# lps22df.net
KiCad netlist of a schematic drawn in Altium Designer
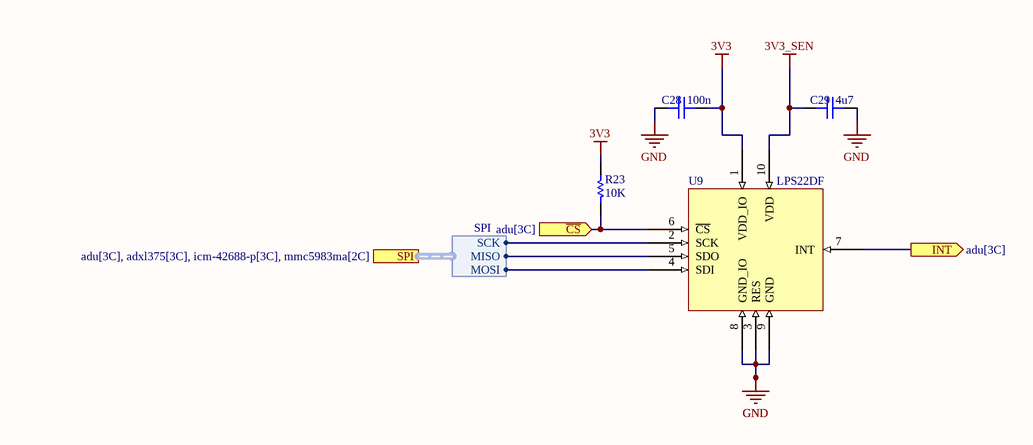
[diagram p0: lps22df.SchDoc]

(export (version "E")
  (design (tool "Eeschema 10.0.6"))
  (components
    (comp (ref "C28")
      (value "100n")
      (footprint "CAP-0603-NP")
      (description "Capacitor")
      (libsource (lib "drfc_schlib") (part "Capacitor"))
    )
    (comp (ref "C29")
      (value "4u7")
      (footprint "CAP-0603-NP")
      (description "Capacitor")
      (libsource (lib "drfc_schlib") (part "Capacitor"))
    )
    (comp (ref "R23")
      (value "10K")
      (footprint "RES-0603")
      (description "Resistor")
      (libsource (lib "drfc_schlib") (part "Resistor"))
    )
    (comp (ref "U9") (value "LPS22DF") (footprint "LPS22DF") (libsource (lib "drfc_schlib") (part "LPS22DF")))
  )
  (nets
    (net (code "2") (name "/INT") (class "Default")
      (node (ref "U9") (pin "7") (pinfunction "INT_7") (pintype "input"))
    )
    (net (code "3") (name "/MISO") (class "Default")
      (node (ref "U9") (pin "5") (pinfunction "SDO_5") (pintype "input"))
    )
    (net (code "4") (name "/MOSI") (class "Default")
      (node (ref "U9") (pin "4") (pinfunction "SDI_4") (pintype "input"))
    )
    (net (code "5") (name "/SCK") (class "Default")
      (node (ref "U9") (pin "2") (pinfunction "SCK_2") (pintype "input"))
    )
    (net (code "7") (name "/~{CS}") (class "Default")
      (node (ref "R23") (pin "1") (pinfunction "1_1") (pintype "passive"))
      (node (ref "U9") (pin "6") (pinfunction "~{CS}_6") (pintype "input"))
    )
    (net (code "8") (name "3V3") (class "Default")
      (node (ref "C28") (pin "2") (pinfunction "2_2") (pintype "passive"))
      (node (ref "R23") (pin "2") (pinfunction "2_2") (pintype "passive"))
      (node (ref "U9") (pin "1") (pinfunction "VDD_IO_1") (pintype "input"))
    )
    (net (code "9") (name "3V3_SEN") (class "Default")
      (node (ref "C29") (pin "1") (pinfunction "1_1") (pintype "passive"))
      (node (ref "U9") (pin "10") (pinfunction "VDD_10") (pintype "input"))
    )
    (net (code "10") (name "GND") (class "Default")
      (node (ref "C28") (pin "1") (pinfunction "1_1") (pintype "passive"))
      (node (ref "C29") (pin "2") (pinfunction "2_2") (pintype "passive"))
      (node (ref "U9") (pin "3") (pinfunction "RES_3") (pintype "input"))
      (node (ref "U9") (pin "8") (pinfunction "GND_IO_8") (pintype "input"))
      (node (ref "U9") (pin "9") (pinfunction "GND_9") (pintype "input"))
    )
  )
)
